# Crystal.net
KiCad netlist of a schematic drawn in Altium Designer
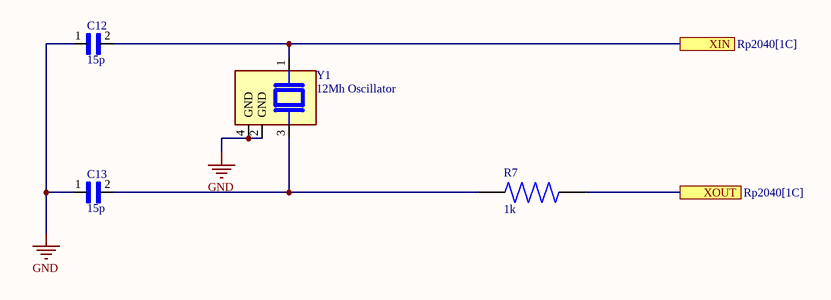
[diagram p0: Crystal.SchDoc]

(export (version "E")
  (design (tool "Eeschema 10.0.6"))
  (components
    (comp (ref "C12")
      (value "15p")
      (footprint "SMD Capacator")
      (libsource (lib "Basic") (part "SMD Capacator"))
    )
    (comp (ref "C13")
      (value "15p")
      (footprint "SMD Capacator")
      (libsource (lib "Basic") (part "SMD Capacator"))
    )
    (comp (ref "R7") (value "1k") (footprint "SMD Resistor") (libsource (lib "Basic") (part "SMD Resistor")))
    (comp (ref "Y1")
      (value "12Mh Oscillator")
      (footprint "12Mh Oscillator")
      (libsource (lib "Basic") (part "12Mh Oscillator"))
    )
  )
  (nets
    (net (code "1") (name "/XIN") (class "Default")
      (node (ref "C12") (pin "2") (pinfunction "2_2") (pintype "passive"))
      (node (ref "Y1") (pin "1") (pinfunction "1_1") (pintype "passive"))
    )
    (net (code "2") (name "/XOUT") (class "Default")
      (node (ref "R7") (pin "2") (pinfunction "2_2") (pintype "passive"))
    )
    (net (code "3") (name "GND") (class "Default")
      (node (ref "C12") (pin "1") (pinfunction "1_1") (pintype "passive"))
      (node (ref "C13") (pin "1") (pinfunction "1_1") (pintype "passive"))
      (node (ref "Y1") (pin "2") (pinfunction "GND_2") (pintype "power_in"))
      (node (ref "Y1") (pin "4") (pinfunction "GND_4") (pintype "power_in"))
    )
    (net (code "4") (name "Net-(Y1-2)") (class "Default")
      (node (ref "C13") (pin "2") (pinfunction "2_2") (pintype "passive"))
      (node (ref "R7") (pin "1") (pinfunction "1_1") (pintype "passive"))
      (node (ref "Y1") (pin "3") (pinfunction "2_3") (pintype "passive"))
    )
  )
)
